# Nacelle_sch.net
KiCad netlist of a schematic drawn in Altium Designer
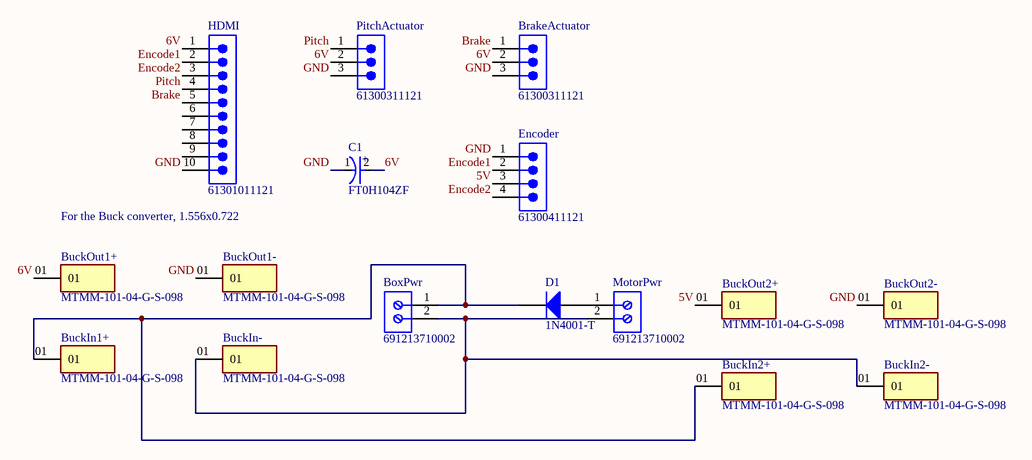
[diagram p0: Nacelle_sch.SchDoc]

(export (version "E")
  (design (tool "Eeschema 10.0.6"))
  (components
    (comp (ref "BoxPwr")
      (value "691213710002")
      (footprint "691213710002")
      (fields (field (name "VOLTAGE") "300V"))
      (libsource (lib "Altium Content Vault") (part "TBL - 1R - 02P - Screw"))
    )
    (comp (ref "BrakeActuator")
      (value "61300311121")
      (footprint "61300311121")
      (libsource (lib "Altium Content Vault") (part "Header_Male_1R_03P"))
    )
    (comp (ref "BuckIn-")
      (value "MTMM-101-04-G-S-098")
      (footprint "SAMTEC_MTMM-101-04-G-S-098")
      (description "Connector Header Through Hole 1 position -")
      (fields (field (name "MF") "Samtec"))
      (libsource (lib "MTMM-101-04-G-S-098") (part "MTMM-101-04-G-S-098"))
    )
    (comp (ref "BuckIn1+")
      (value "MTMM-101-04-G-S-098")
      (footprint "SAMTEC_MTMM-101-04-G-S-098")
      (description "Connector Header Through Hole 1 position -")
      (fields (field (name "MF") "Samtec"))
      (libsource (lib "MTMM-101-04-G-S-098") (part "MTMM-101-04-G-S-098"))
    )
    (comp (ref "BuckIn2+")
      (value "MTMM-101-04-G-S-098")
      (footprint "SAMTEC_MTMM-101-04-G-S-098")
      (description "Connector Header Through Hole 1 position -")
      (fields (field (name "MF") "Samtec"))
      (libsource (lib "MTMM-101-04-G-S-098") (part "MTMM-101-04-G-S-098"))
    )
    (comp (ref "BuckIn2-")
      (value "MTMM-101-04-G-S-098")
      (footprint "SAMTEC_MTMM-101-04-G-S-098")
      (description "Connector Header Through Hole 1 position -")
      (fields (field (name "MF") "Samtec"))
      (libsource (lib "MTMM-101-04-G-S-098") (part "MTMM-101-04-G-S-098"))
    )
    (comp (ref "BuckOut1+")
      (value "MTMM-101-04-G-S-098")
      (footprint "SAMTEC_MTMM-101-04-G-S-098")
      (description "Connector Header Through Hole 1 position -")
      (fields (field (name "MF") "Samtec"))
      (libsource (lib "MTMM-101-04-G-S-098") (part "MTMM-101-04-G-S-098"))
    )
    (comp (ref "BuckOut1-")
      (value "MTMM-101-04-G-S-098")
      (footprint "SAMTEC_MTMM-101-04-G-S-098")
      (description "Connector Header Through Hole 1 position -")
      (fields (field (name "MF") "Samtec"))
      (libsource (lib "MTMM-101-04-G-S-098") (part "MTMM-101-04-G-S-098"))
    )
    (comp (ref "BuckOut2+")
      (value "MTMM-101-04-G-S-098")
      (footprint "SAMTEC_MTMM-101-04-G-S-098")
      (description "Connector Header Through Hole 1 position -")
      (fields (field (name "MF") "Samtec"))
      (libsource (lib "MTMM-101-04-G-S-098") (part "MTMM-101-04-G-S-098"))
    )
    (comp (ref "BuckOut2-")
      (value "MTMM-101-04-G-S-098")
      (footprint "SAMTEC_MTMM-101-04-G-S-098")
      (description "Connector Header Through Hole 1 position -")
      (fields (field (name "MF") "Samtec"))
      (libsource (lib "MTMM-101-04-G-S-098") (part "MTMM-101-04-G-S-098"))
    )
    (comp (ref "C1")
      (value "FT0H104ZF")
      (footprint "FP-FT0H104ZF-MFG")
      (description "CAP 100MF -20% +80% 5.5V T/H")
      (fields
        (field (name "OCTOPART") "https://octopart.com/ft0h104zf-kemet-30531663")
        (field (name "MANUFACTURER") "KEMET")
      )
      (libsource (lib "Altium Content Vault") (part "cf48714ba7e38822c1575c7ec0b6d1f"))
    )
    (comp (ref "D1")
      (value "1N4001-T")
      (footprint "DIOD-DO-41-P-2_V")
      (description "1.0 A Rectifier, 15 pF, 50 V, -65 to 150 degC, 2-Pin DO-41 Plastic, RoHS, Tape and Reel")
      (fields (field (name "MANUFACTURER") "Diodes Inc"))
      (libsource (lib "Altium Content Vault") (part "DIOD-D-A1K2-2"))
    )
    (comp (ref "Encoder")
      (value "61300411121")
      (footprint "61300411121")
      (libsource (lib "Altium Content Vault") (part "Header_Male_1R_04P"))
    )
    (comp (ref "HDMI")
      (value "61301011121")
      (footprint "61301011121")
      (libsource (lib "Altium Content Vault") (part "Header_Male_1R_10P"))
    )
    (comp (ref "MotorPwr")
      (value "691213710002")
      (footprint "691213710002")
      (fields (field (name "VOLTAGE") "300V"))
      (libsource (lib "Altium Content Vault") (part "TBL - 1R - 02P - Screw"))
    )
    (comp (ref "PitchActuator")
      (value "61300311121")
      (footprint "61300311121")
      (libsource (lib "Altium Content Vault") (part "Header_Male_1R_03P"))
    )
  )
  (nets
    (net (code "1") (name "/5V") (class "Default")
      (node (ref "BuckOut2+") (pin "01") (pinfunction "01_01") (pintype "passive"))
      (node (ref "Encoder") (pin "3") (pinfunction "3_3") (pintype "passive"))
    )
    (net (code "2") (name "/6V") (class "Default")
      (node (ref "BrakeActuator") (pin "2") (pinfunction "2_2") (pintype "passive"))
      (node (ref "BuckOut1+") (pin "01") (pinfunction "01_01") (pintype "passive"))
      (node (ref "C1") (pin "2") (pinfunction "A_2") (pintype "passive"))
      (node (ref "HDMI") (pin "1") (pinfunction "1_1") (pintype "passive"))
      (node (ref "PitchActuator") (pin "2") (pinfunction "2_2") (pintype "passive"))
    )
    (net (code "3") (name "/Brake") (class "Default")
      (node (ref "BrakeActuator") (pin "1") (pinfunction "1_1") (pintype "passive"))
      (node (ref "HDMI") (pin "5") (pinfunction "5_5") (pintype "passive"))
    )
    (net (code "4") (name "/Encode1") (class "Default")
      (node (ref "Encoder") (pin "2") (pinfunction "2_2") (pintype "passive"))
      (node (ref "HDMI") (pin "2") (pinfunction "2_2") (pintype "passive"))
    )
    (net (code "5") (name "/Encode2") (class "Default")
      (node (ref "Encoder") (pin "4") (pinfunction "4_4") (pintype "passive"))
      (node (ref "HDMI") (pin "3") (pinfunction "3_3") (pintype "passive"))
    )
    (net (code "6") (name "/GND") (class "Default")
      (node (ref "BrakeActuator") (pin "3") (pinfunction "3_3") (pintype "passive"))
      (node (ref "BuckOut1-") (pin "01") (pinfunction "01_01") (pintype "passive"))
      (node (ref "BuckOut2-") (pin "01") (pinfunction "01_01") (pintype "passive"))
      (node (ref "C1") (pin "1") (pinfunction "C_1") (pintype "passive"))
      (node (ref "Encoder") (pin "1") (pinfunction "1_1") (pintype "passive"))
      (node (ref "HDMI") (pin "10") (pinfunction "10_10") (pintype "passive"))
      (node (ref "PitchActuator") (pin "3") (pinfunction "3_3") (pintype "passive"))
    )
    (net (code "7") (name "/Pitch") (class "Default")
      (node (ref "HDMI") (pin "4") (pinfunction "4_4") (pintype "passive"))
      (node (ref "PitchActuator") (pin "1") (pinfunction "1_1") (pintype "passive"))
    )
    (net (code "8") (name "Net-(BoxPwr-Pad2)") (class "Default")
      (node (ref "BoxPwr") (pin "2") (pinfunction "2_2") (pintype "passive"))
      (node (ref "BuckIn-") (pin "01") (pinfunction "01_01") (pintype "passive"))
      (node (ref "BuckIn2-") (pin "01") (pinfunction "01_01") (pintype "passive"))
      (node (ref "MotorPwr") (pin "2") (pinfunction "2_2") (pintype "passive"))
    )
    (net (code "9") (name "Net-(D1-A)") (class "Default")
      (node (ref "D1") (pin "1") (pinfunction "A_1") (pintype "passive"))
      (node (ref "MotorPwr") (pin "1") (pinfunction "1_1") (pintype "passive"))
    )
    (net (code "10") (name "Net-(D1-K)") (class "Default")
      (node (ref "BoxPwr") (pin "1") (pinfunction "1_1") (pintype "passive"))
      (node (ref "BuckIn1+") (pin "01") (pinfunction "01_01") (pintype "passive"))
      (node (ref "BuckIn2+") (pin "01") (pinfunction "01_01") (pintype "passive"))
      (node (ref "D1") (pin "2") (pinfunction "K_2") (pintype "passive"))
    )
    (net (code "11") (name "unconnected-(HDMI-Pad6)") (class "Default")
      (node (ref "HDMI") (pin "6") (pinfunction "6_6") (pintype "passive"))
    )
    (net (code "12") (name "unconnected-(HDMI-Pad7)") (class "Default")
      (node (ref "HDMI") (pin "7") (pinfunction "7_7") (pintype "passive"))
    )
    (net (code "13") (name "unconnected-(HDMI-Pad8)") (class "Default")
      (node (ref "HDMI") (pin "8") (pinfunction "8_8") (pintype "passive"))
    )
    (net (code "14") (name "unconnected-(HDMI-Pad9)") (class "Default")
      (node (ref "HDMI") (pin "9") (pinfunction "9_9") (pintype "passive"))
    )
  )
)
